# JM_Logics_I2C_SMD_Adapter_v1_4.net
KiCad netlist of a schematic drawn in EAGLE
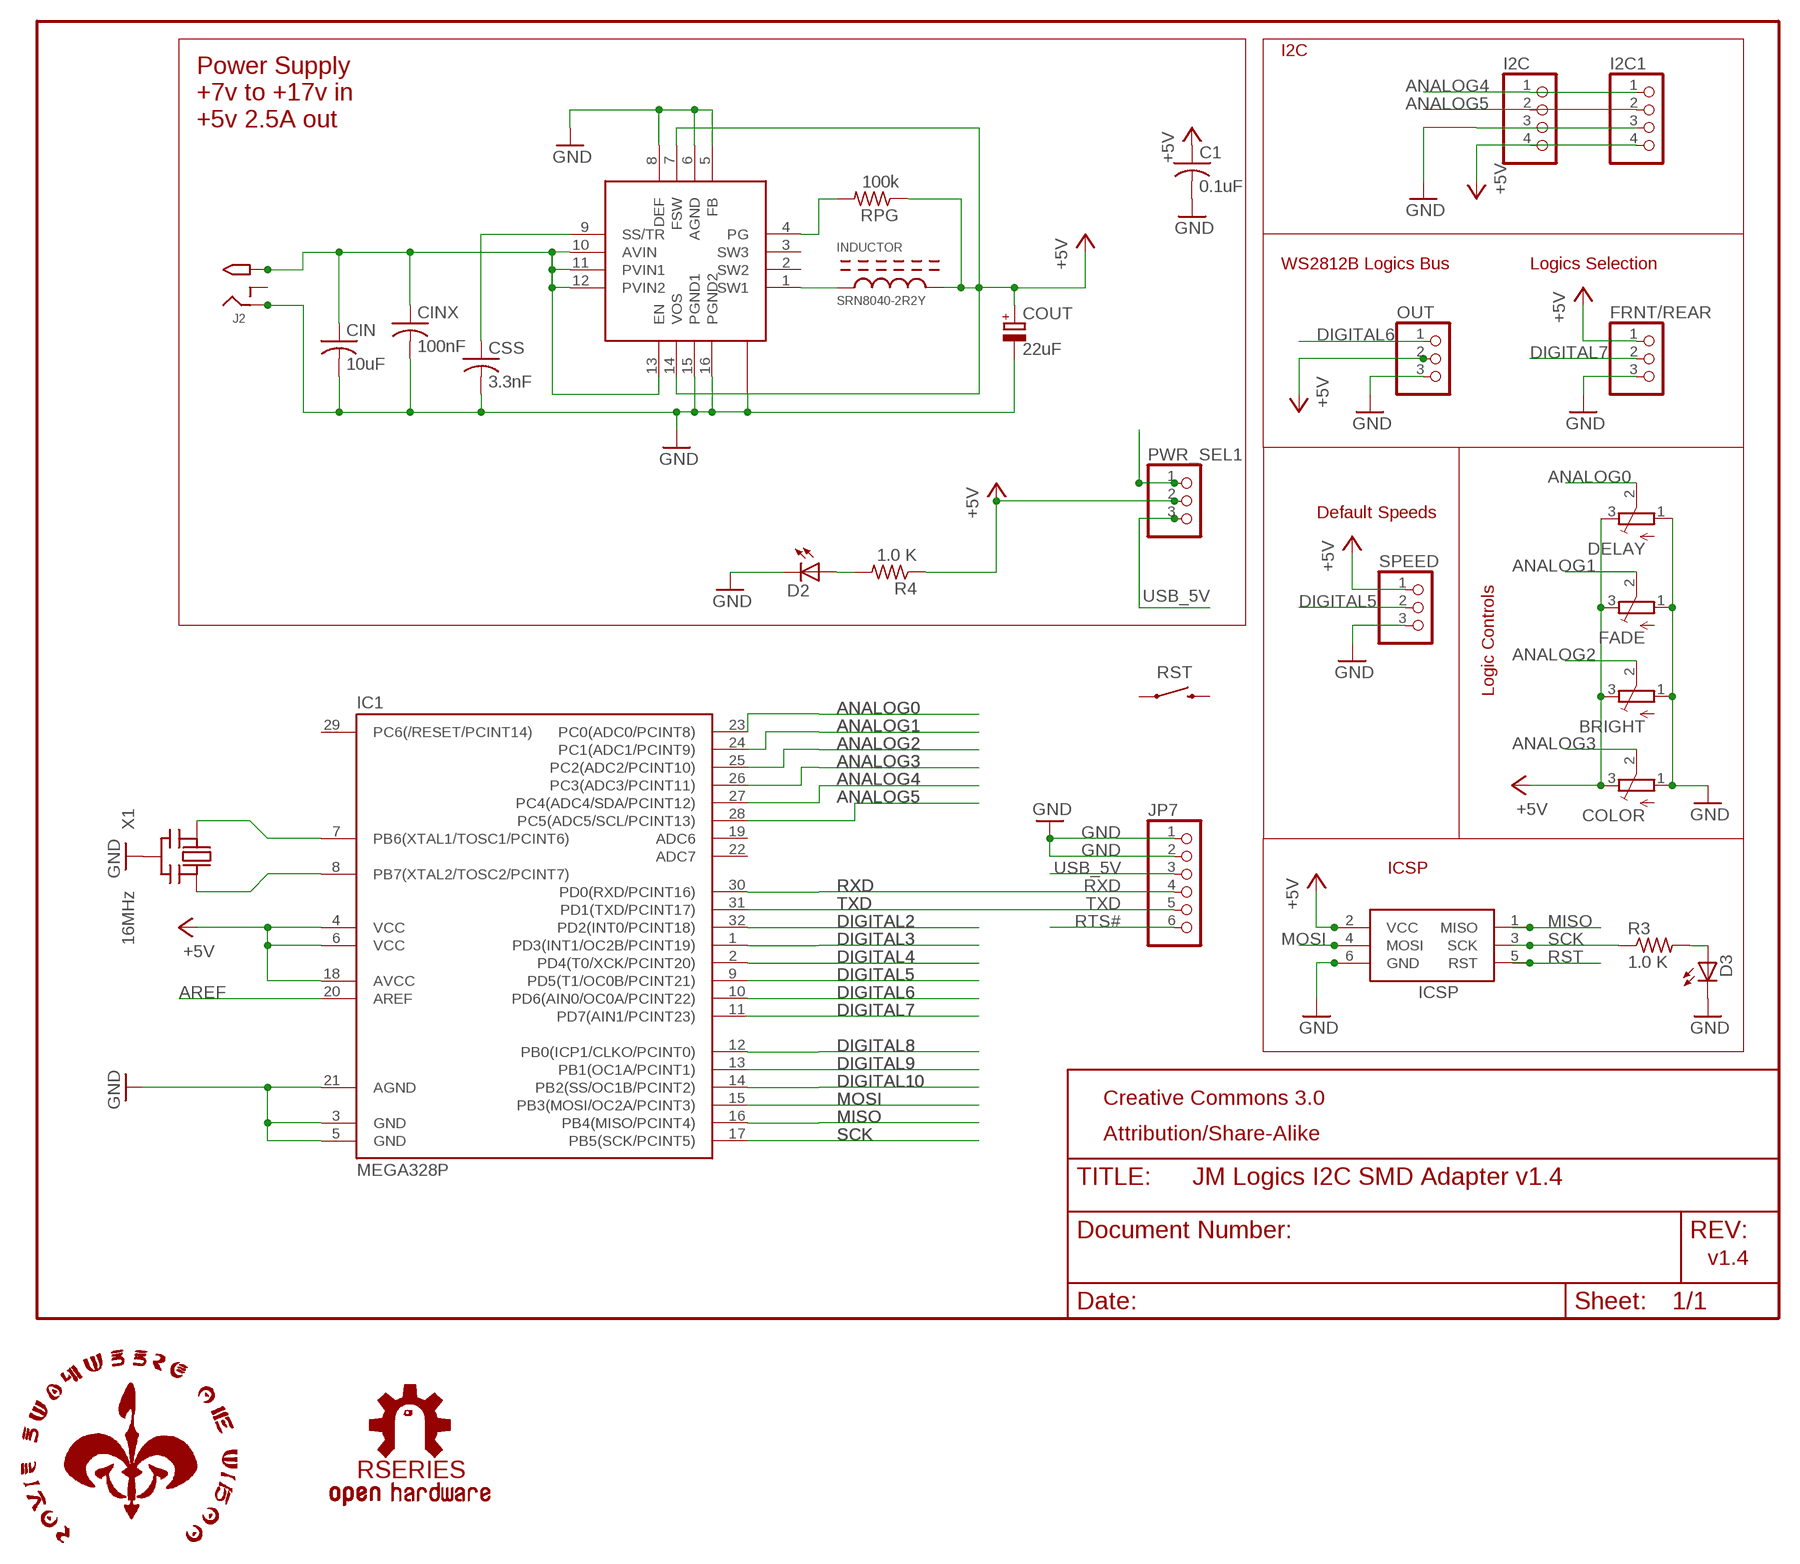
[diagram p0: schematic, sheet 1]

(export (version "E")
  (design (tool "Eeschema 10.0.6"))
  (components
    (comp (ref "BRIGHT")
      (value "TRIMPOTTC33X")
      (footprint "eagle-import:TC33X")
      (libsource (lib "eagle-import") (part "TRIMPOTTC33X"))
    )
    (comp (ref "C1")
      (value "0.1uF")
      (footprint "eagle-import:C1206K")
      (libsource (lib "eagle-import") (part "minimidi_C-USC1206K"))
    )
    (comp (ref "CIN")
      (value "10uF")
      (footprint "eagle-import:C0805K")
      (libsource (lib "eagle-import") (part "C-USC0805K"))
    )
    (comp (ref "CINX")
      (value "100nF")
      (footprint "eagle-import:C0805K")
      (libsource (lib "eagle-import") (part "C-USC0805K"))
    )
    (comp (ref "COLOR")
      (value "TRIMPOTTC33X")
      (footprint "eagle-import:TC33X")
      (libsource (lib "eagle-import") (part "TRIMPOTTC33X"))
    )
    (comp (ref "COUT")
      (value "22uF")
      (footprint "eagle-import:CASE_B")
      (libsource (lib "eagle-import") (part "CAPACITOR_POL-CASE_B"))
    )
    (comp (ref "CSS")
      (value "3.3nF")
      (footprint "eagle-import:C0805K")
      (libsource (lib "eagle-import") (part "C-USC0805K"))
    )
    (comp (ref "D2")
      (value "LEDCHIPLED_1206")
      (footprint "eagle-import:CHIPLED_1206")
      (libsource (lib "eagle-import") (part "LEDCHIPLED_1206"))
    )
    (comp (ref "D3")
      (value "Green")
      (footprint "eagle-import:CHIPLED_1206")
      (libsource (lib "eagle-import") (part "LEDCHIPLED_1206"))
    )
    (comp (ref "DELAY")
      (value "TRIMPOTTC33X")
      (footprint "eagle-import:TC33X")
      (libsource (lib "eagle-import") (part "TRIMPOTTC33X"))
    )
    (comp (ref "FADE")
      (value "TRIMPOTTC33X")
      (footprint "eagle-import:TC33X")
      (libsource (lib "eagle-import") (part "TRIMPOTTC33X"))
    )
    (comp (ref "FRNT/REAR")
      (value "PINHD-1X3")
      (footprint "eagle-import:1X03")
      (libsource (lib "eagle-import") (part "PINHD-1X3"))
    )
    (comp (ref "I2C")
      (value "PINHD-1X4CB")
      (footprint "eagle-import:1X04-CB")
      (libsource (lib "eagle-import") (part "PINHD-1X4CB"))
    )
    (comp (ref "I2C1")
      (value "PINHD-1X4CB")
      (footprint "eagle-import:1X04-CB")
      (libsource (lib "eagle-import") (part "PINHD-1X4CB"))
    )
    (comp (ref "IC1")
      (value "MEGA328P")
      (footprint "eagle-import:TQFP32-08")
      (libsource (lib "eagle-import") (part "MEGA48/88/168-AU"))
    )
    (comp (ref "ICSP")
      (value "AVRISP-6")
      (footprint "eagle-import:AVRISP")
      (libsource (lib "eagle-import") (part "AVRISP-6"))
    )
    (comp (ref "INDUCTOR")
      (value "SRN8040-2R2Y")
      (footprint "eagle-import:SRN8040")
      (libsource (lib "eagle-import") (part "SRN8040"))
    )
    (comp (ref "J2")
      (value "2.1MMJACK")
      (footprint "eagle-import:PJ-102A")
      (libsource (lib "eagle-import") (part "2.1MMJACK"))
    )
    (comp (ref "JP7")
      (value "PINHD-1X6CLEAN")
      (footprint "eagle-import:1X06-CLEAN")
      (libsource (lib "eagle-import") (part "PINHD-1X6CLEAN"))
    )
    (comp (ref "OUT")
      (value "PINHD-1X3")
      (footprint "eagle-import:1X03")
      (libsource (lib "eagle-import") (part "PINHD-1X3"))
    )
    (comp (ref "PWR_SEL1")
      (value "PINHD-1X3")
      (footprint "eagle-import:1X03")
      (libsource (lib "eagle-import") (part "PINHD-1X3"))
    )
    (comp (ref "R3")
      (value "1.0 K")
      (footprint "eagle-import:M1206")
      (libsource (lib "eagle-import") (part "minimidi_R-US_M1206"))
    )
    (comp (ref "R4")
      (value "1.0 K")
      (footprint "eagle-import:M1206")
      (libsource (lib "eagle-import") (part "minimidi_R-US_M1206"))
    )
    (comp (ref "REG")
      (value "TPS62133")
      (footprint "eagle-import:TPS6213X")
      (libsource (lib "eagle-import") (part "TPS6213X"))
    )
    (comp (ref "RPG")
      (value "100k")
      (footprint "eagle-import:R0805")
      (libsource (lib "eagle-import") (part "R-US_R0805"))
    )
    (comp (ref "RST")
      (value "SWITCH-MOMENTARY-2SMD")
      (footprint "eagle-import:TACTILE_SWITCH_SMD")
      (libsource (lib "eagle-import") (part "SWITCH-MOMENTARY-2SMD"))
    )
    (comp (ref "SPEED")
      (value "PINHD-1X3")
      (footprint "eagle-import:1X03")
      (libsource (lib "eagle-import") (part "PINHD-1X3"))
    )
    (comp (ref "U$1")
      (value "ROYAL-ENGINEERS-OF-NABOOSMALL")
      (footprint "eagle-import:ROYAL-ENGINEERS-OF-NABOO-SMALL")
      (libsource (lib "eagle-import") (part "ROYAL-ENGINEERS-OF-NABOOSMALL"))
    )
    (comp (ref "U$2")
      (value "RSERIES-OSHW-LOGOMEDIUM")
      (footprint "eagle-import:RSERIES-OSHW-LOGO-MEDIUM")
      (libsource (lib "eagle-import") (part "RSERIES-OSHW-LOGOMEDIUM"))
    )
    (comp (ref "X1")
      (value "16MHz")
      (footprint "eagle-import:CERM_OSC")
      (libsource (lib "eagle-import") (part "CERMOSCILL"))
    )
  )
  (nets
    (net (code "1") (name "+5V") (class "Default")
      (node (ref "BRIGHT") (pin "3") (pinfunction "E_3") (pintype "passive"))
      (node (ref "C1") (pin "1") (pinfunction "1_1") (pintype "passive"))
      (node (ref "COLOR") (pin "3") (pinfunction "E_3") (pintype "passive"))
      (node (ref "COUT") (pin "+") (pinfunction "+_+") (pintype "passive"))
      (node (ref "DELAY") (pin "3") (pinfunction "E_3") (pintype "passive"))
      (node (ref "FADE") (pin "3") (pinfunction "E_3") (pintype "passive"))
      (node (ref "FRNT/REAR") (pin "1") (pinfunction "1_1") (pintype "passive"))
      (node (ref "I2C") (pin "4") (pinfunction "4_4") (pintype "passive"))
      (node (ref "I2C1") (pin "4") (pinfunction "4_4") (pintype "passive"))
      (node (ref "IC1") (pin "18") (pinfunction "AVCC_18") (pintype "passive"))
      (node (ref "IC1") (pin "4") (pinfunction "VCC_4") (pintype "power_in"))
      (node (ref "IC1") (pin "6") (pinfunction "VCC_6") (pintype "power_in"))
      (node (ref "ICSP") (pin "2") (pinfunction "VCC_2") (pintype "power_in"))
      (node (ref "INDUCTOR") (pin "P$2") (pinfunction "P2_P$2") (pintype "bidirectional"))
      (node (ref "OUT") (pin "2") (pinfunction "2_2") (pintype "passive"))
      (node (ref "PWR_SEL1") (pin "2") (pinfunction "2_2") (pintype "passive"))
      (node (ref "R4") (pin "1") (pinfunction "1_1") (pintype "passive"))
      (node (ref "REG") (pin "14") (pinfunction "VOS_14") (pintype "bidirectional"))
      (node (ref "REG") (pin "7") (pinfunction "FSW_7") (pintype "bidirectional"))
      (node (ref "RPG") (pin "1") (pinfunction "1_1") (pintype "passive"))
      (node (ref "SPEED") (pin "1") (pinfunction "1_1") (pintype "passive"))
    )
    (net (code "2") (name "/ANALOG0") (class "Default")
      (node (ref "DELAY") (pin "2") (pinfunction "S_2") (pintype "passive"))
      (node (ref "IC1") (pin "23") (pinfunction "PC0(ADC0/PCINT8)_23") (pintype "bidirectional"))
    )
    (net (code "3") (name "/ANALOG1") (class "Default")
      (node (ref "FADE") (pin "2") (pinfunction "S_2") (pintype "passive"))
      (node (ref "IC1") (pin "24") (pinfunction "PC1(ADC1/PCINT9)_24") (pintype "bidirectional"))
    )
    (net (code "4") (name "/ANALOG2") (class "Default")
      (node (ref "BRIGHT") (pin "2") (pinfunction "S_2") (pintype "passive"))
      (node (ref "IC1") (pin "25") (pinfunction "PC2(ADC2/PCINT10)_25") (pintype "bidirectional"))
    )
    (net (code "5") (name "/ANALOG3") (class "Default")
      (node (ref "COLOR") (pin "2") (pinfunction "S_2") (pintype "passive"))
      (node (ref "IC1") (pin "26") (pinfunction "PC3(ADC3/PCINT11)_26") (pintype "bidirectional"))
    )
    (net (code "6") (name "/ANALOG4") (class "Default")
      (node (ref "I2C") (pin "1") (pinfunction "1_1") (pintype "passive"))
      (node (ref "I2C1") (pin "1") (pinfunction "1_1") (pintype "passive"))
      (node (ref "IC1") (pin "27") (pinfunction "PC4(ADC4/SDA/PCINT12)_27") (pintype "bidirectional"))
    )
    (net (code "7") (name "/ANALOG5") (class "Default")
      (node (ref "I2C") (pin "2") (pinfunction "2_2") (pintype "passive"))
      (node (ref "I2C1") (pin "2") (pinfunction "2_2") (pintype "passive"))
      (node (ref "IC1") (pin "28") (pinfunction "PC5(ADC5/SCL/PCINT13)_28") (pintype "bidirectional"))
    )
    (net (code "8") (name "/AREF") (class "Default")
      (node (ref "IC1") (pin "20") (pinfunction "AREF_20") (pintype "passive"))
    )
    (net (code "9") (name "/DIGITAL2") (class "Default")
      (node (ref "IC1") (pin "32") (pinfunction "PD2(INT0/PCINT18)_32") (pintype "bidirectional"))
    )
    (net (code "10") (name "/DIGITAL3") (class "Default")
      (node (ref "IC1") (pin "1") (pinfunction "PD3(INT1/OC2B/PCINT19)_1") (pintype "bidirectional"))
    )
    (net (code "11") (name "/DIGITAL4") (class "Default")
      (node (ref "IC1") (pin "2") (pinfunction "PD4(T0/XCK/PCINT20)_2") (pintype "bidirectional"))
    )
    (net (code "12") (name "/DIGITAL5") (class "Default")
      (node (ref "IC1") (pin "9") (pinfunction "PD5(T1/OC0B/PCINT21)_9") (pintype "bidirectional"))
      (node (ref "SPEED") (pin "2") (pinfunction "2_2") (pintype "passive"))
    )
    (net (code "13") (name "/DIGITAL6") (class "Default")
      (node (ref "IC1") (pin "10") (pinfunction "PD6(AIN0/OC0A/PCINT22)_10") (pintype "bidirectional"))
      (node (ref "OUT") (pin "1") (pinfunction "1_1") (pintype "passive"))
    )
    (net (code "14") (name "/DIGITAL7") (class "Default")
      (node (ref "FRNT/REAR") (pin "2") (pinfunction "2_2") (pintype "passive"))
      (node (ref "IC1") (pin "11") (pinfunction "PD7(AIN1/PCINT23)_11") (pintype "bidirectional"))
    )
    (net (code "15") (name "/DIGITAL8") (class "Default")
      (node (ref "IC1") (pin "12") (pinfunction "PB0(ICP1/CLKO/PCINT0)_12") (pintype "bidirectional"))
    )
    (net (code "16") (name "/DIGITAL9") (class "Default")
      (node (ref "IC1") (pin "13") (pinfunction "PB1(OC1A/PCINT1)_13") (pintype "bidirectional"))
    )
    (net (code "17") (name "/DIGITAL10") (class "Default")
      (node (ref "IC1") (pin "14") (pinfunction "PB2(SS/OC1B/PCINT2)_14") (pintype "bidirectional"))
    )
    (net (code "18") (name "/MISO") (class "Default")
      (node (ref "IC1") (pin "16") (pinfunction "PB4(MISO/PCINT4)_16") (pintype "bidirectional"))
      (node (ref "ICSP") (pin "1") (pinfunction "MISO_1") (pintype "input"))
    )
    (net (code "19") (name "/MOSI") (class "Default")
      (node (ref "IC1") (pin "15") (pinfunction "PB3(MOSI/OC2A/PCINT3)_15") (pintype "bidirectional"))
      (node (ref "ICSP") (pin "4") (pinfunction "MOSI_4") (pintype "output"))
    )
    (net (code "20") (name "/RST") (class "Default")
      (node (ref "ICSP") (pin "5") (pinfunction "RST_5") (pintype "output"))
    )
    (net (code "21") (name "/RTS#") (class "Default")
      (node (ref "JP7") (pin "6") (pinfunction "6_6") (pintype "passive"))
    )
    (net (code "22") (name "/RXD") (class "Default")
      (node (ref "IC1") (pin "30") (pinfunction "PD0(RXD/PCINT16)_30") (pintype "bidirectional"))
      (node (ref "JP7") (pin "4") (pinfunction "4_4") (pintype "passive"))
    )
    (net (code "23") (name "/SCK") (class "Default")
      (node (ref "IC1") (pin "17") (pinfunction "PB5(SCK/PCINT5)_17") (pintype "bidirectional"))
      (node (ref "ICSP") (pin "3") (pinfunction "SCK_3") (pintype "output"))
      (node (ref "R3") (pin "1") (pinfunction "1_1") (pintype "passive"))
    )
    (net (code "24") (name "/TXD") (class "Default")
      (node (ref "IC1") (pin "31") (pinfunction "PD1(TXD/PCINT17)_31") (pintype "bidirectional"))
      (node (ref "JP7") (pin "5") (pinfunction "5_5") (pintype "passive"))
    )
    (net (code "25") (name "/USB_5V") (class "Default")
      (node (ref "JP7") (pin "3") (pinfunction "3_3") (pintype "passive"))
      (node (ref "PWR_SEL1") (pin "3") (pinfunction "3_3") (pintype "passive"))
    )
    (net (code "26") (name "GND") (class "Default")
      (node (ref "BRIGHT") (pin "1") (pinfunction "A_1") (pintype "passive"))
      (node (ref "C1") (pin "2") (pinfunction "2_2") (pintype "passive"))
      (node (ref "CIN") (pin "2") (pinfunction "2_2") (pintype "passive"))
      (node (ref "CINX") (pin "2") (pinfunction "2_2") (pintype "passive"))
      (node (ref "COLOR") (pin "1") (pinfunction "A_1") (pintype "passive"))
      (node (ref "COUT") (pin "-") (pinfunction "-_-") (pintype "passive"))
      (node (ref "CSS") (pin "2") (pinfunction "2_2") (pintype "passive"))
      (node (ref "D2") (pin "C") (pinfunction "C_C") (pintype "passive"))
      (node (ref "D3") (pin "C") (pinfunction "C_C") (pintype "passive"))
      (node (ref "DELAY") (pin "1") (pinfunction "A_1") (pintype "passive"))
      (node (ref "FADE") (pin "1") (pinfunction "A_1") (pintype "passive"))
      (node (ref "FRNT/REAR") (pin "3") (pinfunction "3_3") (pintype "passive"))
      (node (ref "I2C") (pin "3") (pinfunction "3_3") (pintype "passive"))
      (node (ref "I2C1") (pin "3") (pinfunction "3_3") (pintype "passive"))
      (node (ref "IC1") (pin "21") (pinfunction "AGND_21") (pintype "power_in"))
      (node (ref "IC1") (pin "3") (pinfunction "GND_3") (pintype "power_in"))
      (node (ref "IC1") (pin "5") (pinfunction "GND_5") (pintype "power_in"))
      (node (ref "ICSP") (pin "6") (pinfunction "GND_6") (pintype "power_in"))
      (node (ref "J2") (pin "RING") (pinfunction "RING_RING") (pintype "bidirectional"))
      (node (ref "JP7") (pin "1") (pinfunction "1_1") (pintype "passive"))
      (node (ref "JP7") (pin "2") (pinfunction "2_2") (pintype "passive"))
      (node (ref "OUT") (pin "3") (pinfunction "3_3") (pintype "passive"))
      (node (ref "REG") (pin "15") (pinfunction "PGND1_15") (pintype "bidirectional"))
      (node (ref "REG") (pin "16") (pinfunction "PGND2_16") (pintype "bidirectional"))
      (node (ref "REG") (pin "17-THERMALPAD") (pinfunction "THERM_17-THERMALPAD") (pintype "bidirectional"))
      (node (ref "REG") (pin "5") (pinfunction "FB_5") (pintype "bidirectional"))
      (node (ref "REG") (pin "6") (pinfunction "AGND_6") (pintype "bidirectional"))
      (node (ref "REG") (pin "8") (pinfunction "DEF_8") (pintype "bidirectional"))
      (node (ref "SPEED") (pin "3") (pinfunction "3_3") (pintype "passive"))
      (node (ref "X1") (pin "P$2") (pinfunction "GND_P$2") (pintype "bidirectional"))
    )
    (net (code "27") (name "Net-(D2-PadA)") (class "Default")
      (node (ref "D2") (pin "A") (pinfunction "A_A") (pintype "passive"))
      (node (ref "R4") (pin "2") (pinfunction "2_2") (pintype "passive"))
    )
    (net (code "28") (name "Net-(D3-PadA)") (class "Default")
      (node (ref "D3") (pin "A") (pinfunction "A_A") (pintype "passive"))
      (node (ref "R3") (pin "2") (pinfunction "2_2") (pintype "passive"))
    )
    (net (code "29") (name "Net-(IC1-PB6(XTAL1{slash}TOSC1{slash}PCINT6))") (class "Default")
      (node (ref "IC1") (pin "7") (pinfunction "PB6(XTAL1/TOSC1/PCINT6)_7") (pintype "bidirectional"))
      (node (ref "X1") (pin "P$1") (pinfunction "IN_P$1") (pintype "bidirectional"))
    )
    (net (code "30") (name "Net-(IC1-PB7(XTAL2{slash}TOSC2{slash}PCINT7))") (class "Default")
      (node (ref "IC1") (pin "8") (pinfunction "PB7(XTAL2/TOSC2/PCINT7)_8") (pintype "bidirectional"))
      (node (ref "X1") (pin "P$3") (pinfunction "OUT_P$3") (pintype "bidirectional"))
    )
    (net (code "31") (name "Net-(INDUCTOR-P1)") (class "Default")
      (node (ref "INDUCTOR") (pin "P$1") (pinfunction "P1_P$1") (pintype "bidirectional"))
      (node (ref "REG") (pin "1") (pinfunction "SW1_1") (pintype "bidirectional"))
    )
    (net (code "32") (name "Net-(REG-AVIN)") (class "Default")
      (node (ref "CIN") (pin "1") (pinfunction "1_1") (pintype "passive"))
      (node (ref "CINX") (pin "1") (pinfunction "1_1") (pintype "passive"))
      (node (ref "J2") (pin "TIP") (pinfunction "TIP_TIP") (pintype "bidirectional"))
      (node (ref "REG") (pin "10") (pinfunction "AVIN_10") (pintype "bidirectional"))
      (node (ref "REG") (pin "11") (pinfunction "PVIN1_11") (pintype "bidirectional"))
      (node (ref "REG") (pin "12") (pinfunction "PVIN2_12") (pintype "bidirectional"))
      (node (ref "REG") (pin "13") (pinfunction "EN_13") (pintype "bidirectional"))
    )
    (net (code "33") (name "Net-(REG-PG)") (class "Default")
      (node (ref "REG") (pin "4") (pinfunction "PG_4") (pintype "bidirectional"))
      (node (ref "RPG") (pin "2") (pinfunction "2_2") (pintype "passive"))
    )
    (net (code "34") (name "Net-(REG-SS{slash}TR)") (class "Default")
      (node (ref "CSS") (pin "1") (pinfunction "1_1") (pintype "passive"))
      (node (ref "REG") (pin "9") (pinfunction "SS/TR_9") (pintype "bidirectional"))
    )
    (net (code "35") (name "unconnected-(IC1-ADC6-Pad19)") (class "Default")
      (node (ref "IC1") (pin "19") (pinfunction "ADC6_19") (pintype "passive"))
    )
    (net (code "36") (name "unconnected-(IC1-ADC7-Pad22)") (class "Default")
      (node (ref "IC1") (pin "22") (pinfunction "ADC7_22") (pintype "passive"))
    )
    (net (code "37") (name "unconnected-(IC1-PC6({slash}RESET{slash}PCINT14)-Pad29)") (class "Default")
      (node (ref "IC1") (pin "29") (pinfunction "PC6(/RESET/PCINT14)_29") (pintype "bidirectional"))
    )
    (net (code "38") (name "unconnected-(J2-PadRING_SW)") (class "Default")
      (node (ref "J2") (pin "RING_SW") (pinfunction "RING_SW_RING_SW") (pintype "bidirectional"))
    )
    (net (code "39") (name "unconnected-(PWR_SEL1-Pad1)") (class "Default")
      (node (ref "PWR_SEL1") (pin "1") (pinfunction "1_1") (pintype "passive"))
    )
    (net (code "40") (name "unconnected-(REG-SW2-Pad2)") (class "Default")
      (node (ref "REG") (pin "2") (pinfunction "SW2_2") (pintype "bidirectional"))
    )
    (net (code "41") (name "unconnected-(REG-SW3-Pad3)") (class "Default")
      (node (ref "REG") (pin "3") (pinfunction "SW3_3") (pintype "bidirectional"))
    )
    (net (code "42") (name "unconnected-(RST-2-Pad3)") (class "Default")
      (node (ref "RST") (pin "3") (pinfunction "2_3") (pintype "passive"))
    )
    (net (code "43") (name "unconnected-(RST-Pad1)") (class "Default")
      (node (ref "RST") (pin "1") (pinfunction "1_1") (pintype "passive"))
    )
  )
)
